# CAN_ADS1015.net
KiCad netlist of a schematic drawn in Altium Designer
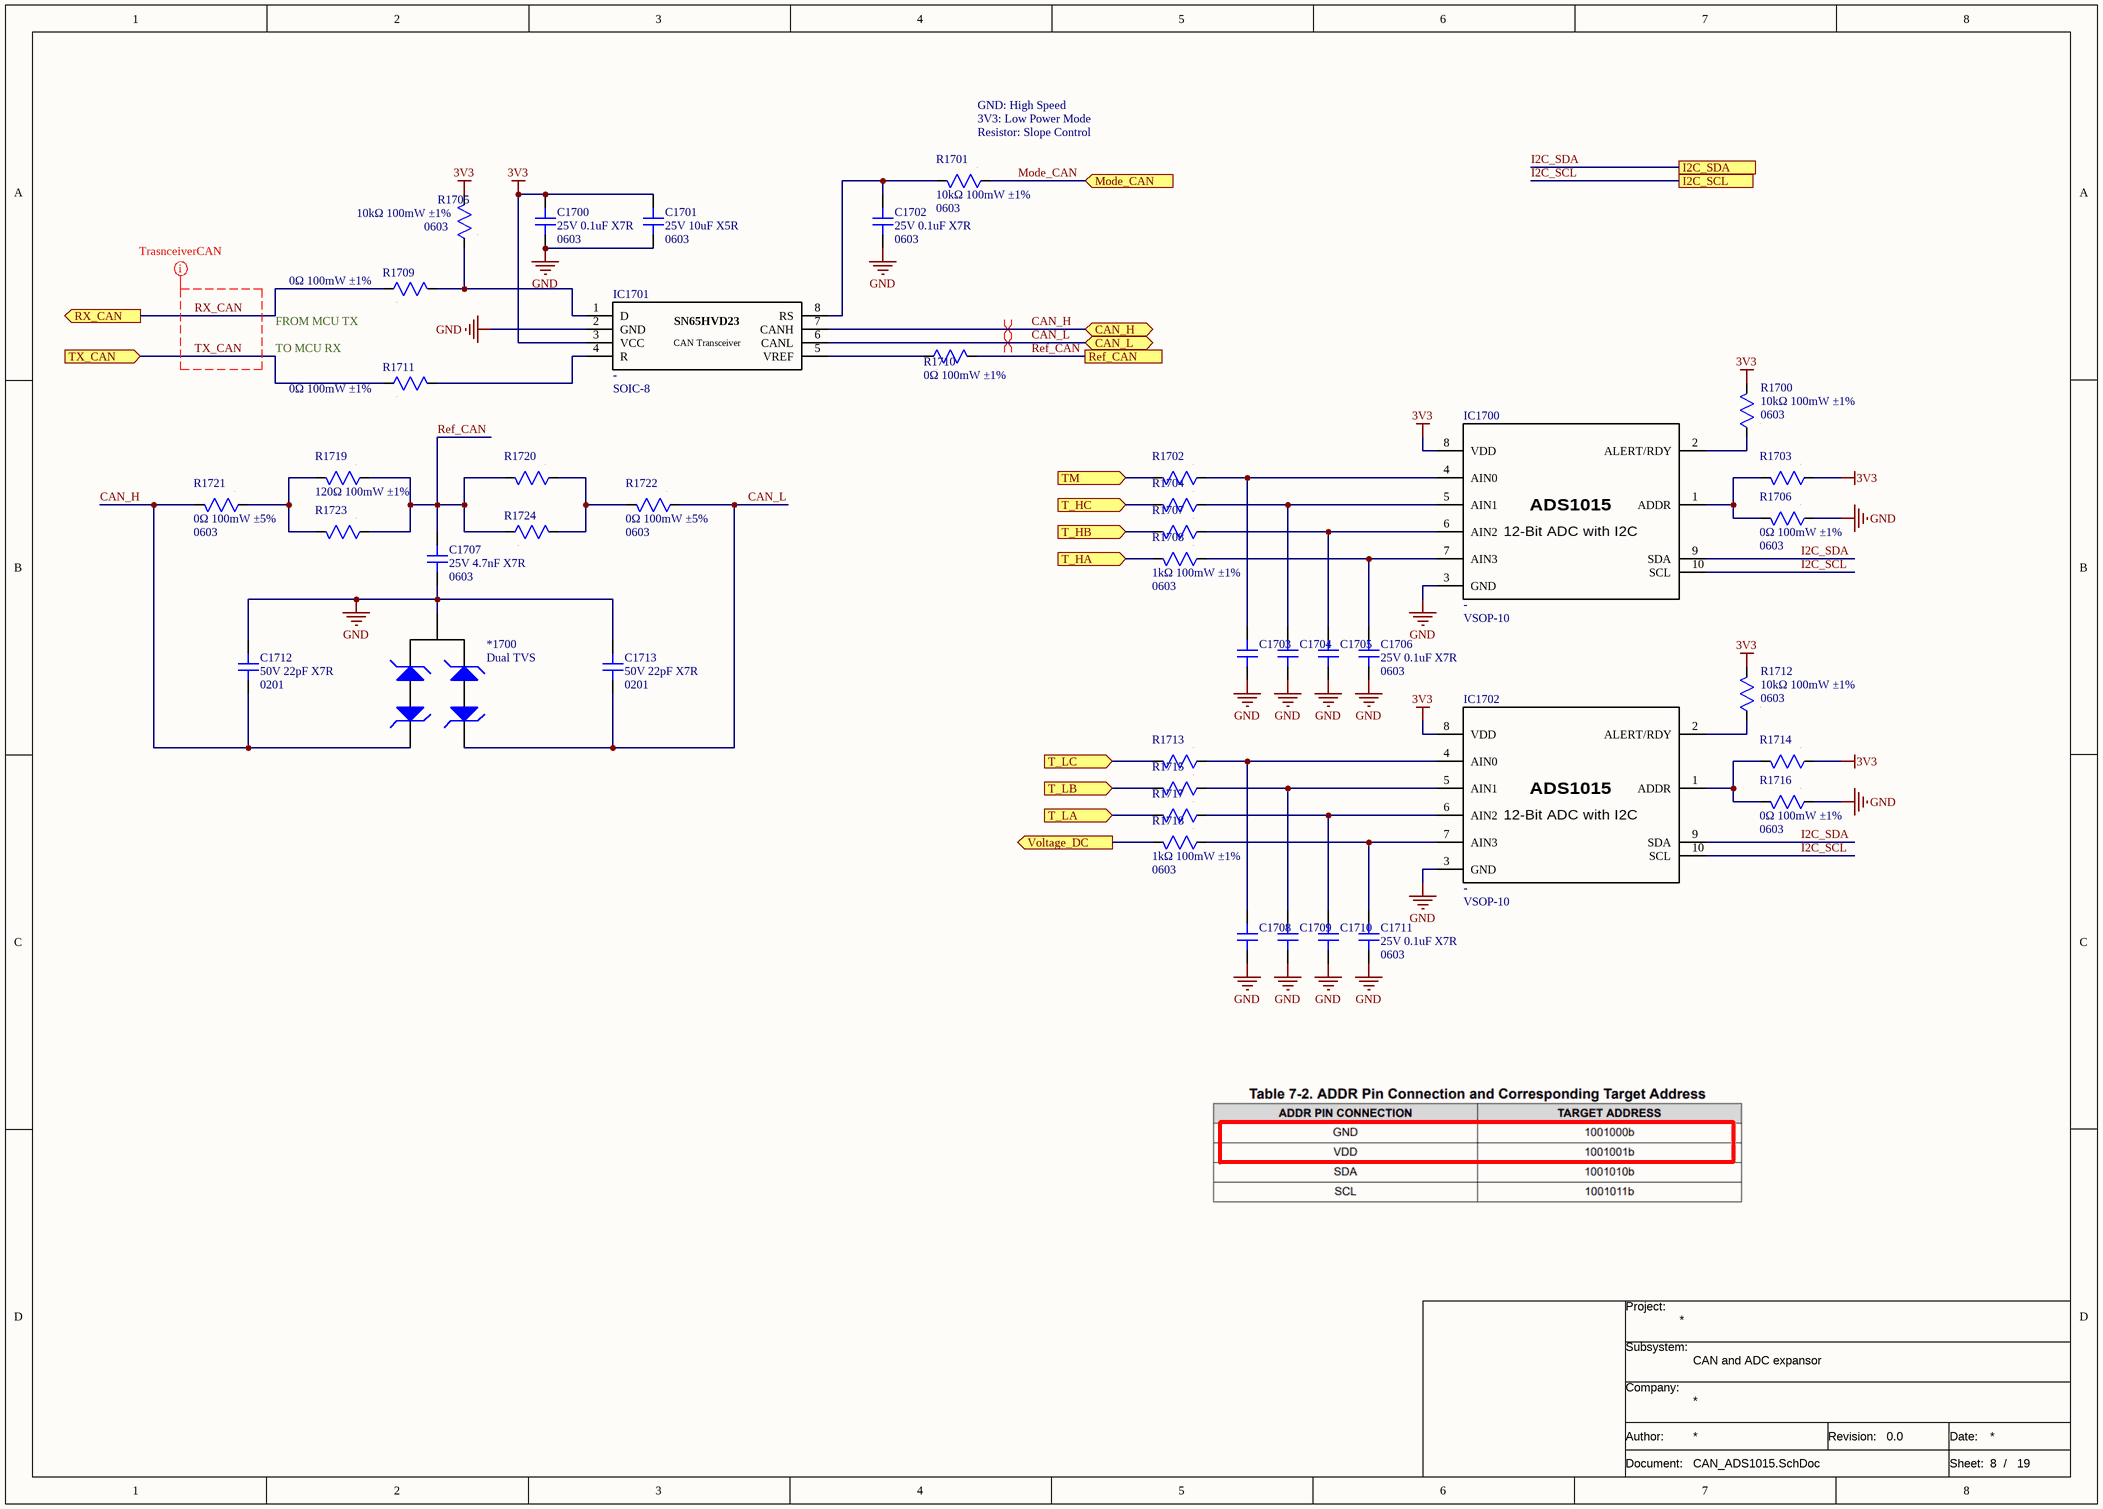
[diagram p0: CAN_ADS1015.SchDoc]

(export (version "E")
  (design (tool "Eeschema 10.0.6"))
  (components
    (comp (ref "*1700")
      (value "Dual TVS")
      (footprint "SOT-23")
      (description "Diodos de Protección contra ESD / Diodos TVS Automotive dual 3- p F +/-24-V +/-30-k")
      (fields (field (name "MPN") "ESD2CAN24DBZRQ1") (field (name "MANUFACTURER") "Texas Instruments"))
      (libsource (lib "eUSR_Database") (part "Dual TVS"))
    )
    (comp (ref "C1700")
      (value "25V 0.1uF X7R")
      (footprint "CAP SMD 0603")
      (description "Condensadores de cerámica multicapa (MLCC- SMD/SMT) WCAP-CSGP 0.1uF 0603 10% 25V MLCC")
      (fields
        (field (name "PACKAGE") "0603")
        (field (name "MPN") "885012206071")
        (field (name "MANUFACTURER") "Wurth Elektronik")
      )
      (libsource (lib "eUSR_Database") (part "CAP non polarized"))
    )
    (comp (ref "C1701")
      (value "25V 10uF X5R")
      (footprint "CAP SMD 0603")
      (description "Condensadores de cerámica multicapa (MLCC- SMD/SMT) 0603 25VDC 10uF 10% X5R")
      (fields
        (field (name "PACKAGE") "0603")
        (field (name "MPN") "ZRB18AR61E106KE01L")
        (field (name "MANUFACTURER") "muRata")
      )
      (libsource (lib "eUSR_Database") (part "CAP non polarized"))
    )
    (comp (ref "C1702")
      (value "25V 0.1uF X7R")
      (footprint "CAP SMD 0603")
      (description "Condensadores de cerámica multicapa (MLCC- SMD/SMT) WCAP-CSGP 0.1uF 0603 10% 25V MLCC")
      (fields
        (field (name "PACKAGE") "0603")
        (field (name "MPN") "885012206071")
        (field (name "MANUFACTURER") "Wurth Elektronik")
      )
      (libsource (lib "eUSR_Database") (part "CAP non polarized"))
    )
    (comp (ref "C1703")
      (value "CAP non polarized")
      (footprint "CAP SMD 0603")
      (description "Condensadores de cerámica multicapa (MLCC- SMD/SMT) WCAP-CSGP 0.1uF 0603 10% 25V MLCC")
      (fields (field (name "MPN") "885012206071") (field (name "MANUFACTURER") "Wurth Elektronik"))
      (libsource (lib "eUSR_Database") (part "CAP non polarized"))
    )
    (comp (ref "C1704")
      (value "CAP non polarized")
      (footprint "CAP SMD 0603")
      (description "Condensadores de cerámica multicapa (MLCC- SMD/SMT) WCAP-CSGP 0.1uF 0603 10% 25V MLCC")
      (fields (field (name "MPN") "885012206071") (field (name "MANUFACTURER") "Wurth Elektronik"))
      (libsource (lib "eUSR_Database") (part "CAP non polarized"))
    )
    (comp (ref "C1705")
      (value "CAP non polarized")
      (footprint "CAP SMD 0603")
      (description "Condensadores de cerámica multicapa (MLCC- SMD/SMT) WCAP-CSGP 0.1uF 0603 10% 25V MLCC")
      (fields (field (name "MPN") "885012206071") (field (name "MANUFACTURER") "Wurth Elektronik"))
      (libsource (lib "eUSR_Database") (part "CAP non polarized"))
    )
    (comp (ref "C1706")
      (value "25V 0.1uF X7R")
      (footprint "CAP SMD 0603")
      (description "Condensadores de cerámica multicapa (MLCC- SMD/SMT) WCAP-CSGP 0.1uF 0603 10% 25V MLCC")
      (fields
        (field (name "PACKAGE") "0603")
        (field (name "MPN") "885012206071")
        (field (name "MANUFACTURER") "Wurth Elektronik")
      )
      (libsource (lib "eUSR_Database") (part "CAP non polarized"))
    )
    (comp (ref "C1707")
      (value "25V 4.7nF X7R")
      (footprint "CAP SMD 0603")
      (description "Condensadores de cerámica multicapa (MLCC- SMD/SMT) WCAP-CSGP 4700pF 0603 10% 25V MLCC")
      (fields
        (field (name "PACKAGE") "0603")
        (field (name "MPN") "885012206063")
        (field (name "MANUFACTURER") "Wurth Elektronik")
      )
      (libsource (lib "eUSR_Database") (part "CAP non polarized"))
    )
    (comp (ref "C1708")
      (value "CAP non polarized")
      (footprint "CAP SMD 0603")
      (description "Condensadores de cerámica multicapa (MLCC- SMD/SMT) WCAP-CSGP 0.1uF 0603 10% 25V MLCC")
      (fields (field (name "MPN") "885012206071") (field (name "MANUFACTURER") "Wurth Elektronik"))
      (libsource (lib "eUSR_Database") (part "CAP non polarized"))
    )
    (comp (ref "C1709")
      (value "CAP non polarized")
      (footprint "CAP SMD 0603")
      (description "Condensadores de cerámica multicapa (MLCC- SMD/SMT) WCAP-CSGP 0.1uF 0603 10% 25V MLCC")
      (fields (field (name "MPN") "885012206071") (field (name "MANUFACTURER") "Wurth Elektronik"))
      (libsource (lib "eUSR_Database") (part "CAP non polarized"))
    )
    (comp (ref "C1710")
      (value "CAP non polarized")
      (footprint "CAP SMD 0603")
      (description "Condensadores de cerámica multicapa (MLCC- SMD/SMT) WCAP-CSGP 0.1uF 0603 10% 25V MLCC")
      (fields (field (name "MPN") "885012206071") (field (name "MANUFACTURER") "Wurth Elektronik"))
      (libsource (lib "eUSR_Database") (part "CAP non polarized"))
    )
    (comp (ref "C1711")
      (value "25V 0.1uF X7R")
      (footprint "CAP SMD 0603")
      (description "Condensadores de cerámica multicapa (MLCC- SMD/SMT) WCAP-CSGP 0.1uF 0603 10% 25V MLCC")
      (fields
        (field (name "PACKAGE") "0603")
        (field (name "MPN") "885012206071")
        (field (name "MANUFACTURER") "Wurth Elektronik")
      )
      (libsource (lib "eUSR_Database") (part "CAP non polarized"))
    )
    (comp (ref "C1712")
      (value "50V 22pF X7R")
      (footprint "CAP SMD 0201")
      (description "Condensadores de cerámica multicapa (MLCC- SMD/SMT) WCAP-CSGP 50VDC 22pF 0201 5%")
      (fields
        (field (name "PACKAGE") "0201")
        (field (name "MPN") "885012004012")
        (field (name "MANUFACTURER") "Wurth Elektronik")
      )
      (libsource (lib "eUSR_Database") (part "CAP non polarized"))
    )
    (comp (ref "C1713")
      (value "50V 22pF X7R")
      (footprint "CAP SMD 0201")
      (description "Condensadores de cerámica multicapa (MLCC- SMD/SMT) WCAP-CSGP 50VDC 22pF 0201 5%")
      (fields
        (field (name "PACKAGE") "0201")
        (field (name "MPN") "885012004012")
        (field (name "MANUFACTURER") "Wurth Elektronik")
      )
      (libsource (lib "eUSR_Database") (part "CAP non polarized"))
    )
    (comp (ref "IC1700")
      (value "-")
      (footprint "VSOP-10")
      (fields
        (field (name "PACKAGE") "VSOP-10")
        (field (name "MPN") "ADS1015IDGSR")
        (field (name "MANUFACTURER") "Texas Instruments")
        (field (name "Comment") "ADS1015")
      )
      (libsource (lib "eUSR_Database") (part "ADS1015"))
    )
    (comp (ref "IC1701")
      (value "-")
      (footprint "SOIC-8")
      (description "Sensores de corriente montados en placa")
      (fields
        (field (name "PACKAGE") "SOIC-8")
        (field (name "MPN") "SN65HVD230DR")
        (field (name "MANUFACTURER") "Texas Instruments")
      )
      (libsource (lib "eUSR_Database") (part "SN65HVD23"))
    )
    (comp (ref "IC1702")
      (value "-")
      (footprint "VSOP-10")
      (fields
        (field (name "PACKAGE") "VSOP-10")
        (field (name "MPN") "ADS1015IDGSR")
        (field (name "MANUFACTURER") "Texas Instruments")
        (field (name "Comment") "ADS1015")
      )
      (libsource (lib "eUSR_Database") (part "ADS1015"))
    )
    (comp (ref "R1700")
      (value "10kΩ 100mW ±1%")
      (footprint "RES SMD 0603")
      (description "Resistores de película gruesa - SMD WRIS-RSKS 10 kOhms 1 % 0.1 W 0603 AEC-Q200")
      (fields
        (field (name "PACKAGE") "0603")
        (field (name "MPN") "560112116005")
        (field (name "MANUFACTURER") "Wurth Elektronik")
      )
      (libsource (lib "eUSR_Database") (part "RES"))
    )
    (comp (ref "R1701")
      (value "10kΩ 100mW ±1%")
      (footprint "RES SMD 0603")
      (description "Resistores de película gruesa - SMD WRIS-RSKS 10 kOhms 1 % 0.1 W 0603 AEC-Q200")
      (fields
        (field (name "PACKAGE") "0603")
        (field (name "MPN") "560112116005")
        (field (name "MANUFACTURER") "Wurth Elektronik")
      )
      (libsource (lib "eUSR_Database") (part "RES"))
    )
    (comp (ref "R1702")
      (value "RES")
      (footprint "RES SMD 0603")
      (description "Thick Film Resistors WRIS-RSKS 1 kOhms 1 % 0.1 W 0603 AEC-Q200")
      (fields (field (name "MPN") "560112116014") (field (name "MANUFACTURER") "Wurth Elektronik"))
      (libsource (lib "eUSR_Database") (part "RES"))
    )
    (comp (ref "R1703")
      (value "RES")
      (footprint "RES SMD 0603")
      (description "Resistores de película gruesa - SMD WRIS-RSKS <0.05 Ohms 0.1 W Jumper 0603 AEC-Q200")
      (fields (field (name "MPN") "560112116001") (field (name "MANUFACTURER") "Wurth Elektronik"))
      (libsource (lib "eUSR_Database") (part "RES"))
    )
    (comp (ref "R1704")
      (value "RES")
      (footprint "RES SMD 0603")
      (description "Thick Film Resistors WRIS-RSKS 1 kOhms 1 % 0.1 W 0603 AEC-Q200")
      (fields (field (name "MPN") "560112116014") (field (name "MANUFACTURER") "Wurth Elektronik"))
      (libsource (lib "eUSR_Database") (part "RES"))
    )
    (comp (ref "R1705")
      (value "10kΩ 100mW ±1%")
      (footprint "RES SMD 0603")
      (description "Resistores de película gruesa - SMD WRIS-RSKS 10 kOhms 1 % 0.1 W 0603 AEC-Q200")
      (fields
        (field (name "PACKAGE") "0603")
        (field (name "MPN") "560112116005")
        (field (name "MANUFACTURER") "Wurth Elektronik")
      )
      (libsource (lib "eUSR_Database") (part "RES"))
    )
    (comp (ref "R1706")
      (value "0Ω 100mW ±1%")
      (footprint "RES SMD 0603")
      (description "Resistores de película gruesa - SMD WRIS-RSKS <0.05 Ohms 0.1 W Jumper 0603 AEC-Q200")
      (fields
        (field (name "PACKAGE") "0603")
        (field (name "MPN") "560112116001")
        (field (name "MANUFACTURER") "Wurth Elektronik")
      )
      (libsource (lib "eUSR_Database") (part "RES"))
    )
    (comp (ref "R1707")
      (value "RES")
      (footprint "RES SMD 0603")
      (description "Thick Film Resistors WRIS-RSKS 1 kOhms 1 % 0.1 W 0603 AEC-Q200")
      (fields (field (name "MPN") "560112116014") (field (name "MANUFACTURER") "Wurth Elektronik"))
      (libsource (lib "eUSR_Database") (part "RES"))
    )
    (comp (ref "R1708")
      (value "1kΩ 100mW ±1%")
      (footprint "RES SMD 0603")
      (description "Thick Film Resistors WRIS-RSKS 1 kOhms 1 % 0.1 W 0603 AEC-Q200")
      (fields
        (field (name "PACKAGE") "0603")
        (field (name "MPN") "560112116014")
        (field (name "MANUFACTURER") "Wurth Elektronik")
      )
      (libsource (lib "eUSR_Database") (part "RES"))
    )
    (comp (ref "R1709")
      (value "0Ω 100mW ±1%")
      (footprint "RES SMD 0603")
      (description "Resistores de película gruesa - SMD WRIS-RSKS <0.05 Ohms 0.1 W Jumper 0603 AEC-Q200")
      (fields (field (name "MPN") "560112116001") (field (name "MANUFACTURER") "Wurth Elektronik"))
      (libsource (lib "eUSR_Database") (part "RES"))
    )
    (comp (ref "R1710")
      (value "0Ω 100mW ±1%")
      (footprint "RES SMD 0603")
      (description "Resistores de película gruesa - SMD WRIS-RSKS <0.05 Ohms 0.1 W Jumper 0603 AEC-Q200")
      (fields (field (name "MPN") "560112116001") (field (name "MANUFACTURER") "Wurth Elektronik"))
      (libsource (lib "eUSR_Database") (part "RES"))
    )
    (comp (ref "R1711")
      (value "0Ω 100mW ±1%")
      (footprint "RES SMD 0603")
      (description "Resistores de película gruesa - SMD WRIS-RSKS <0.05 Ohms 0.1 W Jumper 0603 AEC-Q200")
      (fields (field (name "MPN") "560112116001") (field (name "MANUFACTURER") "Wurth Elektronik"))
      (libsource (lib "eUSR_Database") (part "RES"))
    )
    (comp (ref "R1712")
      (value "10kΩ 100mW ±1%")
      (footprint "RES SMD 0603")
      (description "Resistores de película gruesa - SMD WRIS-RSKS 10 kOhms 1 % 0.1 W 0603 AEC-Q200")
      (fields
        (field (name "PACKAGE") "0603")
        (field (name "MPN") "560112116005")
        (field (name "MANUFACTURER") "Wurth Elektronik")
      )
      (libsource (lib "eUSR_Database") (part "RES"))
    )
    (comp (ref "R1713")
      (value "RES")
      (footprint "RES SMD 0603")
      (description "Thick Film Resistors WRIS-RSKS 1 kOhms 1 % 0.1 W 0603 AEC-Q200")
      (fields (field (name "MPN") "560112116014") (field (name "MANUFACTURER") "Wurth Elektronik"))
      (libsource (lib "eUSR_Database") (part "RES"))
    )
    (comp (ref "R1714")
      (value "RES")
      (footprint "RES SMD 0603")
      (description "Resistores de película gruesa - SMD WRIS-RSKS <0.05 Ohms 0.1 W Jumper 0603 AEC-Q200")
      (fields (field (name "MPN") "560112116001") (field (name "MANUFACTURER") "Wurth Elektronik"))
      (libsource (lib "eUSR_Database") (part "RES"))
    )
    (comp (ref "R1715")
      (value "RES")
      (footprint "RES SMD 0603")
      (description "Thick Film Resistors WRIS-RSKS 1 kOhms 1 % 0.1 W 0603 AEC-Q200")
      (fields (field (name "MPN") "560112116014") (field (name "MANUFACTURER") "Wurth Elektronik"))
      (libsource (lib "eUSR_Database") (part "RES"))
    )
    (comp (ref "R1716")
      (value "0Ω 100mW ±1%")
      (footprint "RES SMD 0603")
      (description "Resistores de película gruesa - SMD WRIS-RSKS <0.05 Ohms 0.1 W Jumper 0603 AEC-Q200")
      (fields
        (field (name "PACKAGE") "0603")
        (field (name "MPN") "560112116001")
        (field (name "MANUFACTURER") "Wurth Elektronik")
      )
      (libsource (lib "eUSR_Database") (part "RES"))
    )
    (comp (ref "R1717")
      (value "RES")
      (footprint "RES SMD 0603")
      (description "Thick Film Resistors WRIS-RSKS 1 kOhms 1 % 0.1 W 0603 AEC-Q200")
      (fields (field (name "MPN") "560112116014") (field (name "MANUFACTURER") "Wurth Elektronik"))
      (libsource (lib "eUSR_Database") (part "RES"))
    )
    (comp (ref "R1718")
      (value "1kΩ 100mW ±1%")
      (footprint "RES SMD 0603")
      (description "Thick Film Resistors WRIS-RSKS 1 kOhms 1 % 0.1 W 0603 AEC-Q200")
      (fields
        (field (name "PACKAGE") "0603")
        (field (name "MPN") "560112116014")
        (field (name "MANUFACTURER") "Wurth Elektronik")
      )
      (libsource (lib "eUSR_Database") (part "RES"))
    )
    (comp (ref "R1719")
      (value "120Ω 100mW ±1%")
      (footprint "RES SMD 0603")
      (description "Resistores de película gruesa - SMD WRIS-RSKS 120 Ohms 1 % 0.1 W 0603 AEC-Q200")
      (fields (field (name "MPN") "560112116119") (field (name "MANUFACTURER") "Wurth Elektronik"))
      (libsource (lib "eUSR_Database") (part "RES"))
    )
    (comp (ref "R1720")
      (value "RES")
      (footprint "RES SMD 0603")
      (description "Resistores de película gruesa - SMD WRIS-RSKS 120 Ohms 1 % 0.1 W 0603 AEC-Q200")
      (fields (field (name "MPN") "560112116119") (field (name "MANUFACTURER") "Wurth Elektronik"))
      (libsource (lib "eUSR_Database") (part "RES"))
    )
    (comp (ref "R1721")
      (value "0Ω 100mW ±5%")
      (footprint "RES SMD 0603")
      (description "Resistores de película gruesa - SMD WRIS-RSKS <0.05 Ohms 0.1 W Jumper 0603 AEC-Q200")
      (fields
        (field (name "PACKAGE") "0603")
        (field (name "MPN") "560112116001")
        (field (name "MANUFACTURER") "Wurth Elektronik")
      )
      (libsource (lib "eUSR_Database") (part "RES"))
    )
    (comp (ref "R1722")
      (value "0Ω 100mW ±5%")
      (footprint "RES SMD 0603")
      (description "Resistores de película gruesa - SMD WRIS-RSKS <0.05 Ohms 0.1 W Jumper 0603 AEC-Q200")
      (fields
        (field (name "PACKAGE") "0603")
        (field (name "MPN") "560112116001")
        (field (name "MANUFACTURER") "Wurth Elektronik")
      )
      (libsource (lib "eUSR_Database") (part "RES"))
    )
    (comp (ref "R1723")
      (value "RES")
      (footprint "RES SMD 0603")
      (description "Resistores de película gruesa - SMD WRIS-RSKS 120 Ohms 1 % 0.1 W 0603 AEC-Q200")
      (fields (field (name "MPN") "560112116119") (field (name "MANUFACTURER") "Wurth Elektronik"))
      (libsource (lib "eUSR_Database") (part "RES"))
    )
    (comp (ref "R1724")
      (value "RES")
      (footprint "RES SMD 0603")
      (description "Resistores de película gruesa - SMD WRIS-RSKS 120 Ohms 1 % 0.1 W 0603 AEC-Q200")
      (fields (field (name "MPN") "560112116119") (field (name "MANUFACTURER") "Wurth Elektronik"))
      (libsource (lib "eUSR_Database") (part "RES"))
    )
  )
  (nets
    (net (code "1") (name "/CAN_H") (class "Default")
      (node (ref "*1700") (pin "1") (pinfunction "1_1") (pintype "passive"))
      (node (ref "C1712") (pin "2") (pinfunction "2_2") (pintype "passive"))
      (node (ref "IC1701") (pin "7") (pinfunction "CANH_7") (pintype "passive"))
      (node (ref "R1721") (pin "2") (pinfunction "2_2") (pintype "passive"))
    )
    (net (code "2") (name "/CAN_L") (class "Default")
      (node (ref "*1700") (pin "2") (pinfunction "2_2") (pintype "passive"))
      (node (ref "C1713") (pin "2") (pinfunction "2_2") (pintype "passive"))
      (node (ref "IC1701") (pin "6") (pinfunction "CANL_6") (pintype "passive"))
      (node (ref "R1722") (pin "1") (pinfunction "1_1") (pintype "passive"))
    )
    (net (code "3") (name "/I2C_SCL") (class "Default")
      (node (ref "IC1700") (pin "10") (pinfunction "SCL_10") (pintype "passive"))
      (node (ref "IC1702") (pin "10") (pinfunction "SCL_10") (pintype "passive"))
    )
    (net (code "4") (name "/I2C_SDA") (class "Default")
      (node (ref "IC1700") (pin "9") (pinfunction "SDA_9") (pintype "passive"))
      (node (ref "IC1702") (pin "9") (pinfunction "SDA_9") (pintype "passive"))
    )
    (net (code "5") (name "/Mode_CAN") (class "Default")
      (node (ref "R1701") (pin "1") (pinfunction "1_1") (pintype "passive"))
    )
    (net (code "6") (name "/RX_CAN") (class "Default")
      (node (ref "R1709") (pin "1") (pinfunction "1_1") (pintype "passive"))
    )
    (net (code "7") (name "/Ref_CAN") (class "Default")
      (node (ref "C1707") (pin "1") (pinfunction "1_1") (pintype "passive"))
      (node (ref "R1710") (pin "2") (pinfunction "2_2") (pintype "passive"))
      (node (ref "R1719") (pin "1") (pinfunction "1_1") (pintype "passive"))
      (node (ref "R1720") (pin "2") (pinfunction "2_2") (pintype "passive"))
      (node (ref "R1723") (pin "1") (pinfunction "1_1") (pintype "passive"))
      (node (ref "R1724") (pin "1") (pinfunction "1_1") (pintype "passive"))
    )
    (net (code "8") (name "/TM") (class "Default")
      (node (ref "R1702") (pin "2") (pinfunction "2_2") (pintype "passive"))
    )
    (net (code "9") (name "/TX_CAN") (class "Default")
      (node (ref "R1711") (pin "1") (pinfunction "1_1") (pintype "passive"))
    )
    (net (code "10") (name "/T_HA") (class "Default")
      (node (ref "R1708") (pin "2") (pinfunction "2_2") (pintype "passive"))
    )
    (net (code "11") (name "/T_HB") (class "Default")
      (node (ref "R1707") (pin "2") (pinfunction "2_2") (pintype "passive"))
    )
    (net (code "12") (name "/T_HC") (class "Default")
      (node (ref "R1704") (pin "2") (pinfunction "2_2") (pintype "passive"))
    )
    (net (code "13") (name "/T_LA") (class "Default")
      (node (ref "R1717") (pin "2") (pinfunction "2_2") (pintype "passive"))
    )
    (net (code "14") (name "/T_LB") (class "Default")
      (node (ref "R1715") (pin "2") (pinfunction "2_2") (pintype "passive"))
    )
    (net (code "15") (name "/T_LC") (class "Default")
      (node (ref "R1713") (pin "2") (pinfunction "2_2") (pintype "passive"))
    )
    (net (code "16") (name "/Voltage_DC") (class "Default")
      (node (ref "R1718") (pin "2") (pinfunction "2_2") (pintype "passive"))
    )
    (net (code "17") (name "3V3") (class "Default")
      (node (ref "C1700") (pin "1") (pinfunction "1_1") (pintype "passive"))
      (node (ref "C1701") (pin "1") (pinfunction "1_1") (pintype "passive"))
      (node (ref "IC1700") (pin "8") (pinfunction "VDD_8") (pintype "power_in"))
      (node (ref "IC1701") (pin "3") (pinfunction "VCC_3") (pintype "passive"))
      (node (ref "IC1702") (pin "8") (pinfunction "VDD_8") (pintype "power_in"))
      (node (ref "R1700") (pin "2") (pinfunction "2_2") (pintype "passive"))
      (node (ref "R1703") (pin "1") (pinfunction "1_1") (pintype "passive"))
      (node (ref "R1705") (pin "2") (pinfunction "2_2") (pintype "passive"))
      (node (ref "R1712") (pin "2") (pinfunction "2_2") (pintype "passive"))
      (node (ref "R1714") (pin "1") (pinfunction "1_1") (pintype "passive"))
    )
    (net (code "18") (name "GND") (class "Default")
      (node (ref "*1700") (pin "3") (pinfunction "3_3") (pintype "passive"))
      (node (ref "C1700") (pin "2") (pinfunction "2_2") (pintype "passive"))
      (node (ref "C1701") (pin "2") (pinfunction "2_2") (pintype "passive"))
      (node (ref "C1702") (pin "2") (pinfunction "2_2") (pintype "passive"))
      (node (ref "C1703") (pin "2") (pinfunction "2_2") (pintype "passive"))
      (node (ref "C1704") (pin "2") (pinfunction "2_2") (pintype "passive"))
      (node (ref "C1705") (pin "2") (pinfunction "2_2") (pintype "passive"))
      (node (ref "C1706") (pin "2") (pinfunction "2_2") (pintype "passive"))
      (node (ref "C1707") (pin "2") (pinfunction "2_2") (pintype "passive"))
      (node (ref "C1708") (pin "2") (pinfunction "2_2") (pintype "passive"))
      (node (ref "C1709") (pin "2") (pinfunction "2_2") (pintype "passive"))
      (node (ref "C1710") (pin "2") (pinfunction "2_2") (pintype "passive"))
      (node (ref "C1711") (pin "2") (pinfunction "2_2") (pintype "passive"))
      (node (ref "C1712") (pin "1") (pinfunction "1_1") (pintype "passive"))
      (node (ref "C1713") (pin "1") (pinfunction "1_1") (pintype "passive"))
      (node (ref "IC1700") (pin "3") (pinfunction "GND_3") (pintype "power_in"))
      (node (ref "IC1701") (pin "2") (pinfunction "GND_2") (pintype "passive"))
      (node (ref "IC1702") (pin "3") (pinfunction "GND_3") (pintype "power_in"))
      (node (ref "R1706") (pin "1") (pinfunction "1_1") (pintype "passive"))
      (node (ref "R1716") (pin "1") (pinfunction "1_1") (pintype "passive"))
    )
    (net (code "19") (name "Net-(IC1700-ADDR)") (class "Default")
      (node (ref "IC1700") (pin "1") (pinfunction "ADDR_1") (pintype "passive"))
      (node (ref "R1703") (pin "2") (pinfunction "2_2") (pintype "passive"))
      (node (ref "R1706") (pin "2") (pinfunction "2_2") (pintype "passive"))
    )
    (net (code "20") (name "Net-(IC1700-AIN0)") (class "Default")
      (node (ref "C1703") (pin "1") (pinfunction "1_1") (pintype "passive"))
      (node (ref "IC1700") (pin "4") (pinfunction "AIN0_4") (pintype "passive"))
      (node (ref "R1702") (pin "1") (pinfunction "1_1") (pintype "passive"))
    )
    (net (code "21") (name "Net-(IC1700-AIN1)") (class "Default")
      (node (ref "C1704") (pin "1") (pinfunction "1_1") (pintype "passive"))
      (node (ref "IC1700") (pin "5") (pinfunction "AIN1_5") (pintype "passive"))
      (node (ref "R1704") (pin "1") (pinfunction "1_1") (pintype "passive"))
    )
    (net (code "22") (name "Net-(IC1700-AIN2)") (class "Default")
      (node (ref "C1705") (pin "1") (pinfunction "1_1") (pintype "passive"))
      (node (ref "IC1700") (pin "6") (pinfunction "AIN2_6") (pintype "passive"))
      (node (ref "R1707") (pin "1") (pinfunction "1_1") (pintype "passive"))
    )
    (net (code "23") (name "Net-(IC1700-AIN3)") (class "Default")
      (node (ref "C1706") (pin "1") (pinfunction "1_1") (pintype "passive"))
      (node (ref "IC1700") (pin "7") (pinfunction "AIN3_7") (pintype "passive"))
      (node (ref "R1708") (pin "1") (pinfunction "1_1") (pintype "passive"))
    )
    (net (code "24") (name "Net-(IC1700-ALERT{slash}RDY)") (class "Default")
      (node (ref "IC1700") (pin "2") (pinfunction "ALERT/RDY_2") (pintype "passive"))
      (node (ref "R1700") (pin "1") (pinfunction "1_1") (pintype "passive"))
    )
    (net (code "25") (name "Net-(IC1701-D)") (class "Default")
      (node (ref "IC1701") (pin "1") (pinfunction "D_1") (pintype "passive"))
      (node (ref "R1705") (pin "1") (pinfunction "1_1") (pintype "passive"))
      (node (ref "R1709") (pin "2") (pinfunction "2_2") (pintype "passive"))
    )
    (net (code "26") (name "Net-(IC1701-R)") (class "Default")
      (node (ref "IC1701") (pin "4") (pinfunction "R_4") (pintype "passive"))
      (node (ref "R1711") (pin "2") (pinfunction "2_2") (pintype "passive"))
    )
    (net (code "27") (name "Net-(IC1701-RS)") (class "Default")
      (node (ref "C1702") (pin "1") (pinfunction "1_1") (pintype "passive"))
      (node (ref "IC1701") (pin "8") (pinfunction "RS_8") (pintype "passive"))
      (node (ref "R1701") (pin "2") (pinfunction "2_2") (pintype "passive"))
    )
    (net (code "28") (name "Net-(IC1701-VREF)") (class "Default")
      (node (ref "IC1701") (pin "5") (pinfunction "VREF_5") (pintype "passive"))
      (node (ref "R1710") (pin "1") (pinfunction "1_1") (pintype "passive"))
    )
    (net (code "29") (name "Net-(IC1702-ADDR)") (class "Default")
      (node (ref "IC1702") (pin "1") (pinfunction "ADDR_1") (pintype "passive"))
      (node (ref "R1714") (pin "2") (pinfunction "2_2") (pintype "passive"))
      (node (ref "R1716") (pin "2") (pinfunction "2_2") (pintype "passive"))
    )
    (net (code "30") (name "Net-(IC1702-AIN0)") (class "Default")
      (node (ref "C1708") (pin "1") (pinfunction "1_1") (pintype "passive"))
      (node (ref "IC1702") (pin "4") (pinfunction "AIN0_4") (pintype "passive"))
      (node (ref "R1713") (pin "1") (pinfunction "1_1") (pintype "passive"))
    )
    (net (code "31") (name "Net-(IC1702-AIN1)") (class "Default")
      (node (ref "C1709") (pin "1") (pinfunction "1_1") (pintype "passive"))
      (node (ref "IC1702") (pin "5") (pinfunction "AIN1_5") (pintype "passive"))
      (node (ref "R1715") (pin "1") (pinfunction "1_1") (pintype "passive"))
    )
    (net (code "32") (name "Net-(IC1702-AIN2)") (class "Default")
      (node (ref "C1710") (pin "1") (pinfunction "1_1") (pintype "passive"))
      (node (ref "IC1702") (pin "6") (pinfunction "AIN2_6") (pintype "passive"))
      (node (ref "R1717") (pin "1") (pinfunction "1_1") (pintype "passive"))
    )
    (net (code "33") (name "Net-(IC1702-AIN3)") (class "Default")
      (node (ref "C1711") (pin "1") (pinfunction "1_1") (pintype "passive"))
      (node (ref "IC1702") (pin "7") (pinfunction "AIN3_7") (pintype "passive"))
      (node (ref "R1718") (pin "1") (pinfunction "1_1") (pintype "passive"))
    )
    (net (code "34") (name "Net-(IC1702-ALERT{slash}RDY)") (class "Default")
      (node (ref "IC1702") (pin "2") (pinfunction "ALERT/RDY_2") (pintype "passive"))
      (node (ref "R1712") (pin "1") (pinfunction "1_1") (pintype "passive"))
    )
    (net (code "35") (name "Net-(R1719-Pad2)") (class "Default")
      (node (ref "R1719") (pin "2") (pinfunction "2_2") (pintype "passive"))
      (node (ref "R1721") (pin "1") (pinfunction "1_1") (pintype "passive"))
      (node (ref "R1723") (pin "2") (pinfunction "2_2") (pintype "passive"))
    )
    (net (code "36") (name "Net-(R1720-Pad1)") (class "Default")
      (node (ref "R1720") (pin "1") (pinfunction "1_1") (pintype "passive"))
      (node (ref "R1722") (pin "2") (pinfunction "2_2") (pintype "passive"))
      (node (ref "R1724") (pin "2") (pinfunction "2_2") (pintype "passive"))
    )
  )
)
